# mic_bobV1.net
KiCad netlist of a schematic drawn in EAGLE
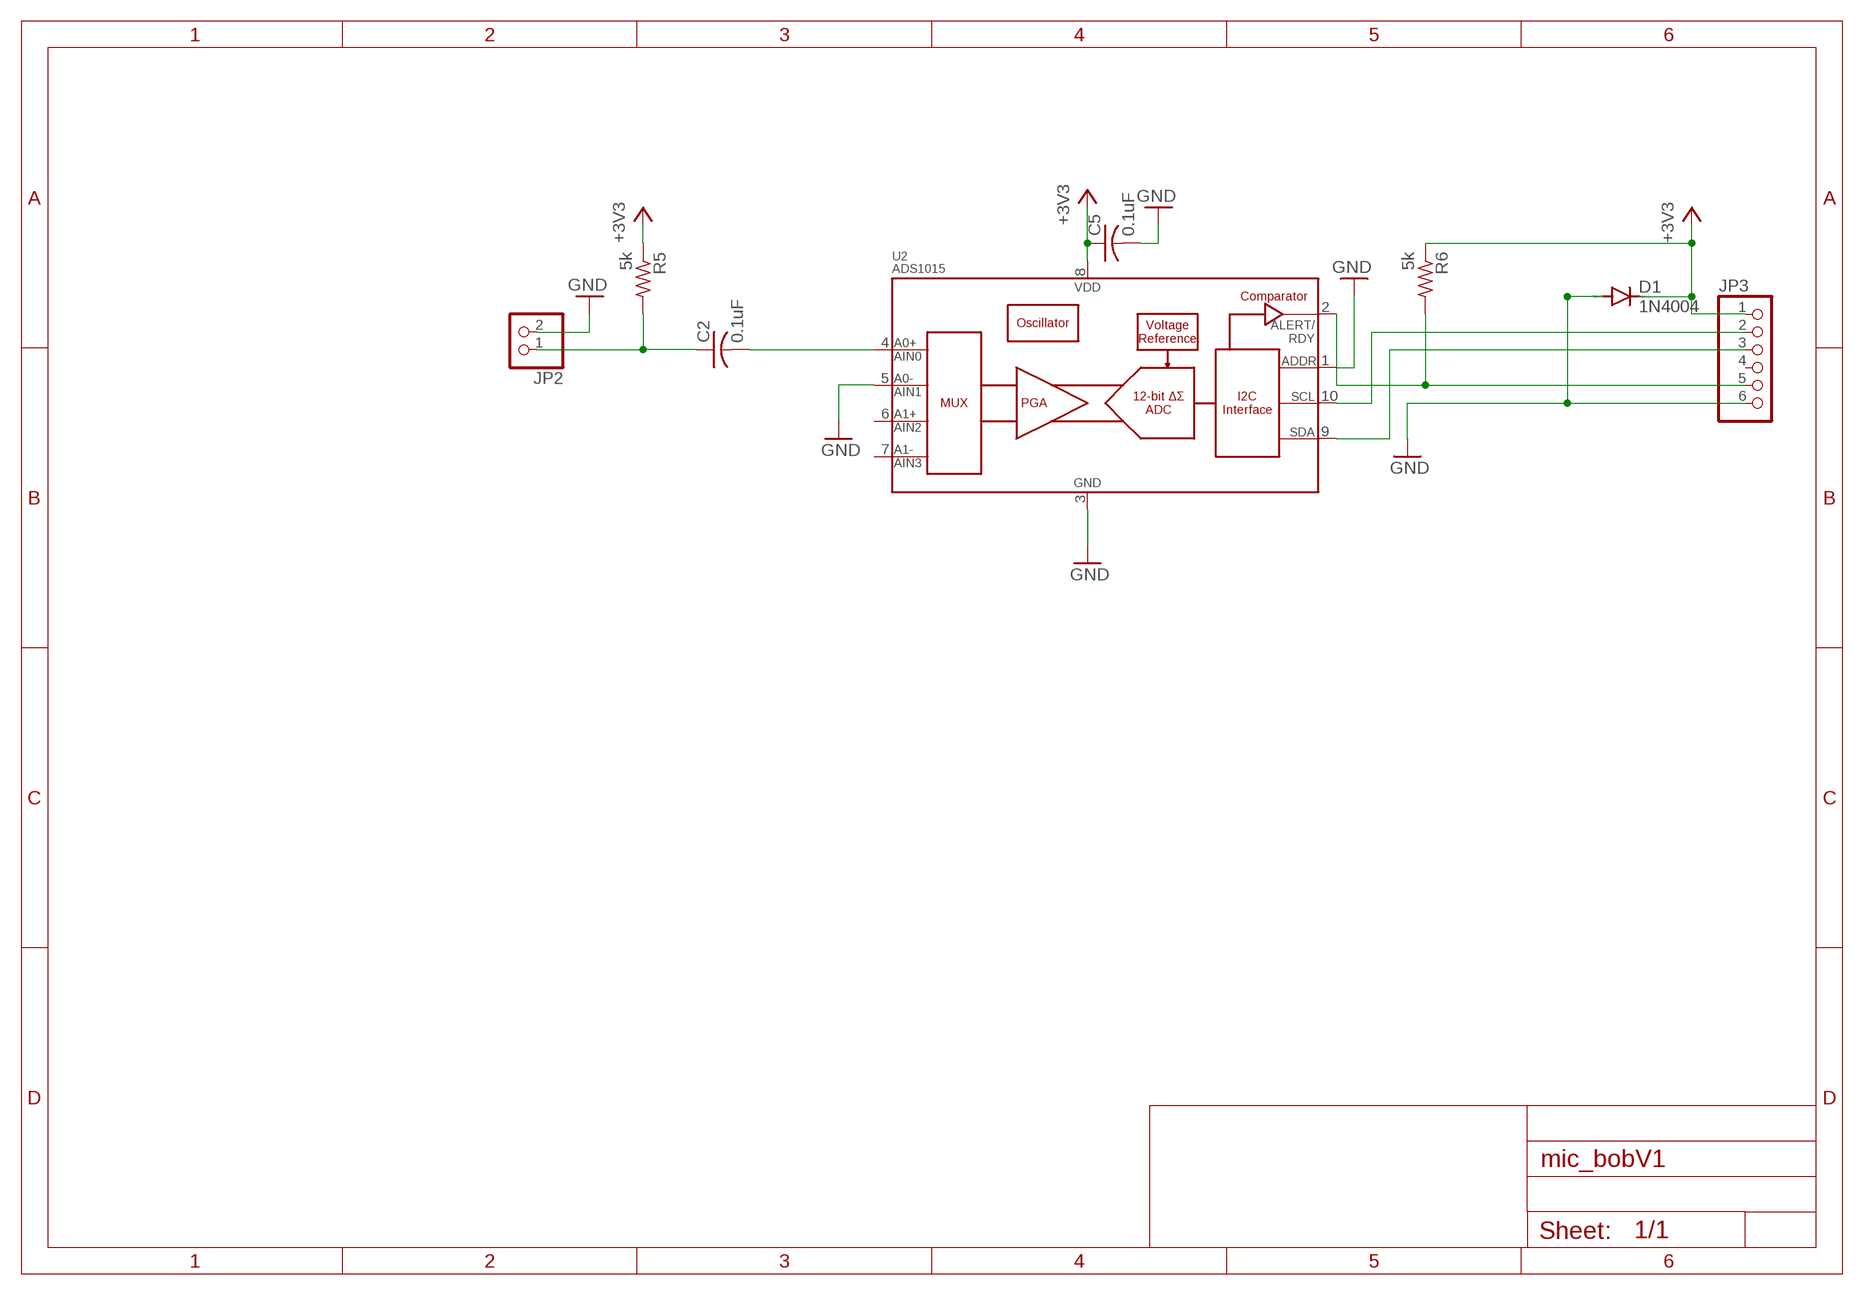
[diagram p0: schematic, sheet 1]

(export (version "E")
  (design (tool "Eeschema 10.0.6"))
  (components
    (comp (ref "C2")
      (value "0.1uF")
      (footprint "eagle-import:C1206")
      (libsource (lib "eagle-import") (part "C-USC1206"))
    )
    (comp (ref "C5")
      (value "0.1uF")
      (footprint "eagle-import:C1206")
      (libsource (lib "eagle-import") (part "C-USC1206"))
    )
    (comp (ref "D1")
      (value "1N4004")
      (footprint "eagle-import:DO41-10")
      (libsource (lib "eagle-import") (part "1N4004"))
    )
    (comp (ref "JP2")
      (value "PINHD-1X2")
      (footprint "eagle-import:1X02")
      (libsource (lib "eagle-import") (part "PINHD-1X2"))
    )
    (comp (ref "JP3")
      (value "PINHD-1X6")
      (footprint "eagle-import:1X06")
      (libsource (lib "eagle-import") (part "PINHD-1X6"))
    )
    (comp (ref "R5")
      (value "5k")
      (footprint "eagle-import:0207_10")
      (libsource (lib "eagle-import") (part "R-US_0207/10"))
    )
    (comp (ref "R6")
      (value "5k")
      (footprint "eagle-import:0207_10")
      (libsource (lib "eagle-import") (part "R-US_0207/10"))
    )
    (comp (ref "U2")
      (value "ADS1015")
      (footprint "eagle-import:MSOP10")
      (libsource (lib "eagle-import") (part "ADS1015"))
    )
  )
  (nets
    (net (code "1") (name "+3V3") (class "Default")
      (node (ref "C5") (pin "1") (pinfunction "1_1") (pintype "passive"))
      (node (ref "D1") (pin "C") (pinfunction "C_C") (pintype "passive"))
      (node (ref "JP3") (pin "1") (pinfunction "1_1") (pintype "passive"))
      (node (ref "R5") (pin "1") (pinfunction "1_1") (pintype "passive"))
      (node (ref "R6") (pin "1") (pinfunction "1_1") (pintype "passive"))
      (node (ref "U2") (pin "8") (pinfunction "VDD_8") (pintype "bidirectional"))
    )
    (net (code "2") (name "GND") (class "Default")
      (node (ref "C5") (pin "2") (pinfunction "2_2") (pintype "passive"))
      (node (ref "D1") (pin "A") (pinfunction "A_A") (pintype "passive"))
      (node (ref "JP2") (pin "2") (pinfunction "2_2") (pintype "passive"))
      (node (ref "JP3") (pin "6") (pinfunction "6_6") (pintype "passive"))
      (node (ref "U2") (pin "1") (pinfunction "ADDR_1") (pintype "bidirectional"))
      (node (ref "U2") (pin "3") (pinfunction "VSS_3") (pintype "bidirectional"))
      (node (ref "U2") (pin "5") (pinfunction "AIN1_5") (pintype "bidirectional"))
    )
    (net (code "3") (name "Net-(C2-Pad1)") (class "Default")
      (node (ref "C2") (pin "1") (pinfunction "1_1") (pintype "passive"))
      (node (ref "JP2") (pin "1") (pinfunction "1_1") (pintype "passive"))
      (node (ref "R5") (pin "2") (pinfunction "2_2") (pintype "passive"))
    )
    (net (code "4") (name "Net-(U2-AIN0)") (class "Default")
      (node (ref "C2") (pin "2") (pinfunction "2_2") (pintype "passive"))
      (node (ref "U2") (pin "4") (pinfunction "AIN0_4") (pintype "bidirectional"))
    )
    (net (code "5") (name "Net-(U2-ALERT{slash}RDY)") (class "Default")
      (node (ref "JP3") (pin "5") (pinfunction "5_5") (pintype "passive"))
      (node (ref "R6") (pin "2") (pinfunction "2_2") (pintype "passive"))
      (node (ref "U2") (pin "2") (pinfunction "ALERT/RDY_2") (pintype "bidirectional"))
    )
    (net (code "6") (name "Net-(U2-SCL)") (class "Default")
      (node (ref "JP3") (pin "2") (pinfunction "2_2") (pintype "passive"))
      (node (ref "U2") (pin "10") (pinfunction "SCL_10") (pintype "bidirectional"))
    )
    (net (code "7") (name "Net-(U2-SDA)") (class "Default")
      (node (ref "JP3") (pin "3") (pinfunction "3_3") (pintype "passive"))
      (node (ref "U2") (pin "9") (pinfunction "SDA_9") (pintype "bidirectional"))
    )
    (net (code "8") (name "unconnected-(JP3-Pad4)") (class "Default")
      (node (ref "JP3") (pin "4") (pinfunction "4_4") (pintype "passive"))
    )
    (net (code "9") (name "unconnected-(U2-AIN2-Pad6)") (class "Default")
      (node (ref "U2") (pin "6") (pinfunction "AIN2_6") (pintype "bidirectional"))
    )
    (net (code "10") (name "unconnected-(U2-AIN3-Pad7)") (class "Default")
      (node (ref "U2") (pin "7") (pinfunction "AIN3_7") (pintype "bidirectional"))
    )
  )
)
